# HBridge.net
KiCad netlist of a schematic drawn in Altium Designer
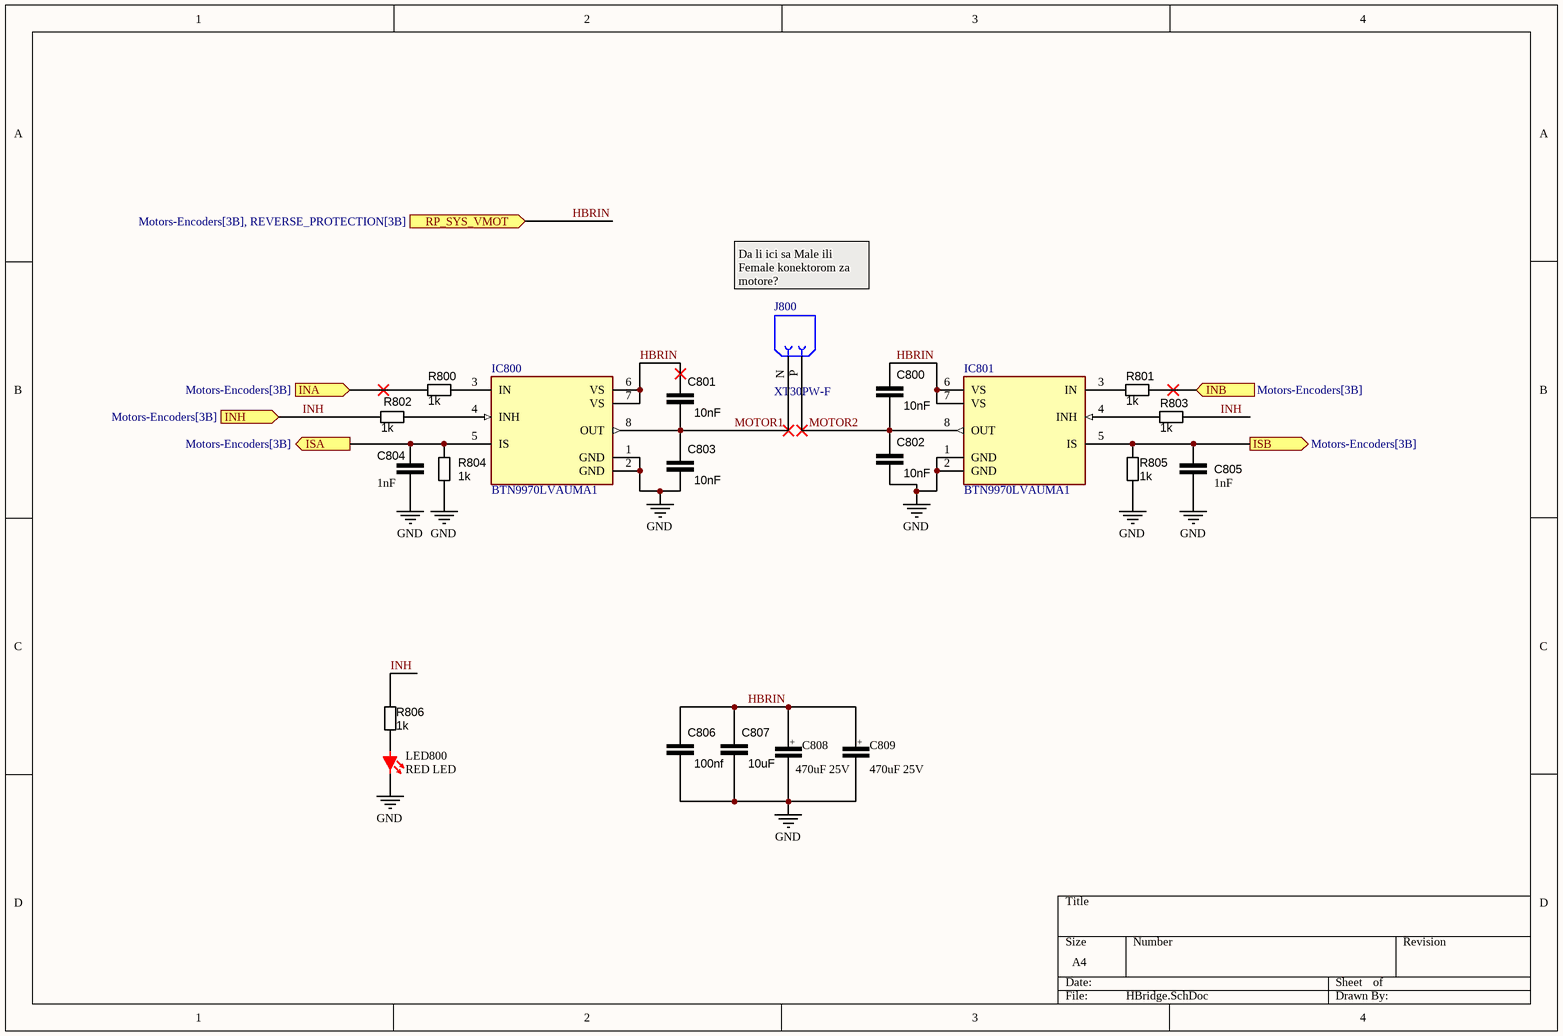
[diagram p0: HBridge.SchDoc]

(export (version "E")
  (design (tool "Eeschema 10.0.6"))
  (components
    (comp (ref "C800")
      (value "10nF")
      (footprint "CAP_0603")
      (description "CAP CER 10nF 0603 25V X7R")
      (libsource (lib "CapacitorsIntegrated") (part "C000007"))
    )
    (comp (ref "C801")
      (value "10nF")
      (footprint "CAP_0603")
      (description "CAP CER 10nF 0603 25V X7R")
      (libsource (lib "CapacitorsIntegrated") (part "C000007"))
    )
    (comp (ref "C802")
      (value "10nF")
      (footprint "CAP_0603")
      (description "CAP CER 10nF 0603 25V X7R")
      (libsource (lib "CapacitorsIntegrated") (part "C000007"))
    )
    (comp (ref "C803")
      (value "10nF")
      (footprint "CAP_0603")
      (description "CAP CER 10nF 0603 25V X7R")
      (libsource (lib "CapacitorsIntegrated") (part "C000007"))
    )
    (comp (ref "C804")
      (value "1nF")
      (footprint "CAP_0603")
      (description "CAP CER 1nF 0603 25V X7R")
      (fields (field (name "DIGIKEY PART NUMBER") "478-KGM15ACG1E820FTCT-ND"))
      (libsource (lib "CapacitorsIntegrated") (part "C000021"))
    )
    (comp (ref "C805")
      (value "1nF")
      (footprint "CAP_0603")
      (description "CAP CER 1nF 0603 25V X7R")
      (fields (field (name "DIGIKEY PART NUMBER") "478-KGM15ACG1E820FTCT-ND"))
      (libsource (lib "") (part "C000021_1"))
    )
    (comp (ref "C806")
      (value "100nf")
      (footprint "CAP_0603")
      (description "CAP CER 100nF 0603 25V X7R")
      (libsource (lib "CapacitorsIntegrated") (part "C000007"))
    )
    (comp (ref "C807")
      (value "10uF")
      (footprint "CAP_0603")
      (description "CAP CER 10uF 0603 25V X7R")
      (libsource (lib "CapacitorsIntegrated") (part "C000007"))
    )
    (comp (ref "C808")
      (value "470uF 25V")
      (footprint "WCAP-ATG5_8X11.5(DXL)")
      (fields
        (field (name "MF") "{'manufacturer': u'~{W}xfcrth Elektronik'}")
        (field (name "MP") "860020474014")
      )
      (libsource (lib "860020474014") (part "WCAP-ATG5_8X11.5"))
    )
    (comp (ref "C809")
      (value "470uF 25V")
      (footprint "WCAP-ATG5_8X11.5(DXL)")
      (fields
        (field (name "MF") "{'manufacturer': u'~{W}xfcrth Elektronik'}")
        (field (name "MP") "860020474014")
      )
      (libsource (lib "860020474014") (part "WCAP-ATG5_8X11.5"))
    )
    (comp (ref "IC800")
      (value "BTN9970LVAUMA1")
      (footprint "FP-PG-HSOF-7-MFG")
      (description "DC_MOTOR_CONTROL PG-HSOF-7")
      (libsource (lib "Altium Content Vault") (part "34e90cea5ba01f3343ad3be64cd8383"))
    )
    (comp (ref "IC801")
      (value "BTN9970LVAUMA1")
      (footprint "FP-PG-HSOF-7-MFG")
      (description "DC_MOTOR_CONTROL PG-HSOF-7")
      (libsource (lib "") (part "34e90cea5ba01f3343ad3be64cd8383_1"))
    )
    (comp (ref "J800")
      (value "XT30PW-F")
      (footprint "AMASS_XT30PW-F")
      (fields (field (name "MF") "{'manufacturer': u'amass'}"))
      (libsource (lib "SnapEDA_Library2") (part "XT30PW-F"))
    )
    (comp (ref "LED800")
      (value "RED LED")
      (footprint "DIOC1608X04N-RED")
      (description "LED RED DIFFUSED 0603 SMD")
      (libsource (lib "Miscellaneous_Lib1") (part "00000008"))
    )
    (comp (ref "R800")
      (value "1k")
      (footprint "RES_0603")
      (description "RES 1k OHM 1% 1/10W 0603")
      (libsource (lib "") (part "R000004_1"))
    )
    (comp (ref "R801")
      (value "1k")
      (footprint "RES_0603")
      (description "RES 1k OHM 1% 1/10W 0603")
      (libsource (lib "") (part "R000004_2"))
    )
    (comp (ref "R802")
      (value "1k")
      (footprint "RES_0603")
      (description "RES 1k OHM 1% 1/10W 0603")
      (libsource (lib "") (part "R000004_1"))
    )
    (comp (ref "R803")
      (value "1k")
      (footprint "RES_0603")
      (description "RES 1k OHM 1% 1/10W 0603")
      (libsource (lib "") (part "R000004_2"))
    )
    (comp (ref "R804")
      (value "1k")
      (footprint "RES_0603")
      (description "RES 1k OHM 1% 1/10W 0603")
      (libsource (lib "ResistorsIntegrated") (part "R000004"))
    )
    (comp (ref "R805")
      (value "1k")
      (footprint "RES_0603")
      (description "RES 1k OHM 1% 1/10W 0603")
      (libsource (lib "") (part "R000004_1"))
    )
    (comp (ref "R806")
      (value "1k")
      (footprint "RES_0603")
      (description "RES 1k OHM 1% 1/10W 0603")
      (libsource (lib "ResistorsIntegrated") (part "R000004"))
    )
  )
  (nets
    (net (code "1") (name "/HBRIN") (class "Default")
      (node (ref "C800") (pin "2") (pinfunction "2_2") (pintype "passive"))
      (node (ref "C801") (pin "2") (pinfunction "2_2") (pintype "passive"))
      (node (ref "C806") (pin "2") (pinfunction "2_2") (pintype "passive"))
      (node (ref "C807") (pin "2") (pinfunction "2_2") (pintype "passive"))
      (node (ref "C808") (pin "1") (pinfunction "POS_1") (pintype "passive"))
      (node (ref "C809") (pin "1") (pinfunction "POS_1") (pintype "passive"))
      (node (ref "IC800") (pin "6") (pinfunction "VS_6") (pintype "power_in"))
      (node (ref "IC800") (pin "7") (pinfunction "VS_7") (pintype "power_in"))
      (node (ref "IC801") (pin "6") (pinfunction "VS_6") (pintype "power_in"))
      (node (ref "IC801") (pin "7") (pinfunction "VS_7") (pintype "power_in"))
    )
    (net (code "2") (name "/INA") (class "Default")
      (node (ref "R800") (pin "2") (pinfunction "2_2") (pintype "passive"))
    )
    (net (code "3") (name "/INB") (class "Default")
      (node (ref "R801") (pin "2") (pinfunction "2_2") (pintype "passive"))
    )
    (net (code "4") (name "/INH") (class "Default")
      (node (ref "R802") (pin "2") (pinfunction "2_2") (pintype "passive"))
      (node (ref "R803") (pin "2") (pinfunction "2_2") (pintype "passive"))
      (node (ref "R806") (pin "1") (pinfunction "1_1") (pintype "passive"))
    )
    (net (code "5") (name "/ISA") (class "Default")
      (node (ref "C804") (pin "2") (pinfunction "2_2") (pintype "passive"))
      (node (ref "IC800") (pin "5") (pinfunction "IS_5") (pintype "passive"))
      (node (ref "R804") (pin "1") (pinfunction "1_1") (pintype "passive"))
    )
    (net (code "6") (name "/ISB") (class "Default")
      (node (ref "C805") (pin "2") (pinfunction "2_2") (pintype "passive"))
      (node (ref "IC801") (pin "5") (pinfunction "IS_5") (pintype "passive"))
      (node (ref "R805") (pin "1") (pinfunction "1_1") (pintype "passive"))
    )
    (net (code "7") (name "/MOTOR1") (class "Default")
      (node (ref "C801") (pin "1") (pinfunction "1_1") (pintype "passive"))
      (node (ref "C803") (pin "2") (pinfunction "2_2") (pintype "passive"))
      (node (ref "IC800") (pin "8") (pinfunction "OUT_8") (pintype "output"))
      (node (ref "J800") (pin "N") (pinfunction "N_N") (pintype "power_in"))
    )
    (net (code "8") (name "/MOTOR2") (class "Default")
      (node (ref "C800") (pin "1") (pinfunction "1_1") (pintype "passive"))
      (node (ref "C802") (pin "2") (pinfunction "2_2") (pintype "passive"))
      (node (ref "IC801") (pin "8") (pinfunction "OUT_8") (pintype "output"))
      (node (ref "J800") (pin "P") (pinfunction "P_P") (pintype "power_in"))
    )
    (net (code "9") (name "GND") (class "Default")
      (node (ref "C802") (pin "1") (pinfunction "1_1") (pintype "passive"))
      (node (ref "C803") (pin "1") (pinfunction "1_1") (pintype "passive"))
      (node (ref "C804") (pin "1") (pinfunction "1_1") (pintype "passive"))
      (node (ref "C805") (pin "1") (pinfunction "1_1") (pintype "passive"))
      (node (ref "C806") (pin "1") (pinfunction "1_1") (pintype "passive"))
      (node (ref "C807") (pin "1") (pinfunction "1_1") (pintype "passive"))
      (node (ref "C808") (pin "2") (pinfunction "NEG_2") (pintype "passive"))
      (node (ref "C809") (pin "2") (pinfunction "NEG_2") (pintype "passive"))
      (node (ref "IC800") (pin "1") (pinfunction "GND_1") (pintype "power_in"))
      (node (ref "IC800") (pin "2") (pinfunction "GND_2") (pintype "power_in"))
      (node (ref "IC801") (pin "1") (pinfunction "GND_1") (pintype "power_in"))
      (node (ref "IC801") (pin "2") (pinfunction "GND_2") (pintype "power_in"))
      (node (ref "LED800") (pin "2") (pinfunction "2_2") (pintype "passive"))
      (node (ref "R804") (pin "2") (pinfunction "2_2") (pintype "passive"))
      (node (ref "R805") (pin "2") (pinfunction "2_2") (pintype "passive"))
    )
    (net (code "10") (name "Net-(IC800-IN)") (class "Default")
      (node (ref "IC800") (pin "3") (pinfunction "IN_3") (pintype "power_in"))
      (node (ref "R800") (pin "1") (pinfunction "1_1") (pintype "passive"))
    )
    (net (code "11") (name "Net-(IC800-INH)") (class "Default")
      (node (ref "IC800") (pin "4") (pinfunction "INH_4") (pintype "input"))
      (node (ref "R802") (pin "1") (pinfunction "1_1") (pintype "passive"))
    )
    (net (code "12") (name "Net-(IC801-IN)") (class "Default")
      (node (ref "IC801") (pin "3") (pinfunction "IN_3") (pintype "power_in"))
      (node (ref "R801") (pin "1") (pinfunction "1_1") (pintype "passive"))
    )
    (net (code "13") (name "Net-(IC801-INH)") (class "Default")
      (node (ref "IC801") (pin "4") (pinfunction "INH_4") (pintype "input"))
      (node (ref "R803") (pin "1") (pinfunction "1_1") (pintype "passive"))
    )
    (net (code "14") (name "Net-(LED800-Pad1)") (class "Default")
      (node (ref "LED800") (pin "1") (pinfunction "1_1") (pintype "passive"))
      (node (ref "R806") (pin "2") (pinfunction "2_2") (pintype "passive"))
    )
  )
)
